# ATtiny4313_PN532_I2CMUX.net
KiCad netlist of a schematic drawn in EAGLE
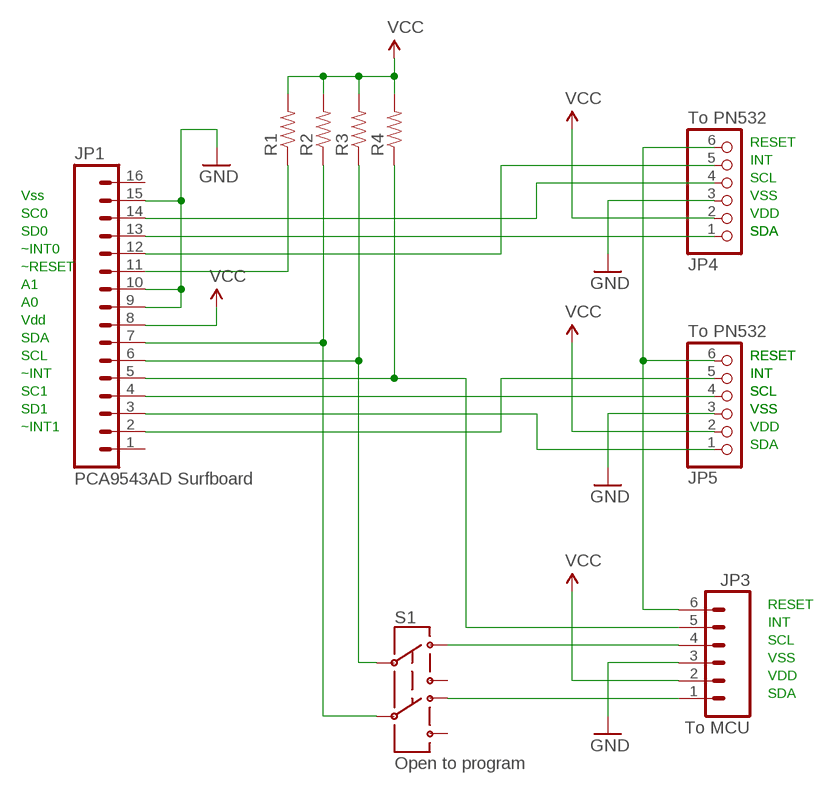
[diagram p0: schematic, sheet 1]

(export (version "E")
  (design (tool "Eeschema 10.0.6"))
  (components
    (comp (ref "JP1")
      (value "PCA9543AD Surfboard")
      (footprint "eagle-import:1X16_MACHINE-PIN-HEADER_LOCK.004")
      (libsource (lib "eagle-import") (part "M16MACHIINE-PIN_LOCK"))
    )
    (comp (ref "JP3")
      (value "To MCU")
      (footprint "eagle-import:1X06_LONGPADS")
      (libsource (lib "eagle-import") (part "M06LONGPADS"))
    )
    (comp (ref "JP4")
      (value "To PN532")
      (footprint "eagle-import:1X06_90")
      (libsource (lib "eagle-import") (part "PINHD-1X6/90"))
    )
    (comp (ref "JP5")
      (value "To PN532")
      (footprint "eagle-import:1X06_90")
      (libsource (lib "eagle-import") (part "PINHD-1X6/90"))
    )
    (comp (ref "R1")
      (value "RESISTORAXIAL-0.3")
      (footprint "eagle-import:AXIAL-0.3")
      (libsource (lib "eagle-import") (part "RESISTORAXIAL-0.3"))
    )
    (comp (ref "R2")
      (value "RESISTORAXIAL-0.3")
      (footprint "eagle-import:AXIAL-0.3")
      (libsource (lib "eagle-import") (part "RESISTORAXIAL-0.3"))
    )
    (comp (ref "R3")
      (value "RESISTORAXIAL-0.3")
      (footprint "eagle-import:AXIAL-0.3")
      (libsource (lib "eagle-import") (part "RESISTORAXIAL-0.3"))
    )
    (comp (ref "R4")
      (value "RESISTORAXIAL-0.3")
      (footprint "eagle-import:AXIAL-0.3")
      (libsource (lib "eagle-import") (part "RESISTORAXIAL-0.3"))
    )
    (comp (ref "S1")
      (value "Open to program")
      (footprint "eagle-import:OS")
      (libsource (lib "eagle-import") (part "SWITCH-DPDTOS"))
    )
  )
  (nets
    (net (code "1") (name "GND") (class "Default")
      (node (ref "JP1") (pin "10") (pinfunction "10_10") (pintype "passive"))
      (node (ref "JP1") (pin "15") (pinfunction "15_15") (pintype "passive"))
      (node (ref "JP1") (pin "9") (pinfunction "9_9") (pintype "passive"))
      (node (ref "JP3") (pin "3") (pinfunction "3_3") (pintype "passive"))
      (node (ref "JP4") (pin "3") (pinfunction "3_3") (pintype "passive"))
      (node (ref "JP5") (pin "3") (pinfunction "3_3") (pintype "passive"))
    )
    (net (code "2") (name "Net-(JP1-Pad2)") (class "Default")
      (node (ref "JP1") (pin "2") (pinfunction "2_2") (pintype "passive"))
      (node (ref "JP5") (pin "5") (pinfunction "5_5") (pintype "passive"))
    )
    (net (code "3") (name "Net-(JP1-Pad3)") (class "Default")
      (node (ref "JP1") (pin "3") (pinfunction "3_3") (pintype "passive"))
      (node (ref "JP5") (pin "1") (pinfunction "1_1") (pintype "passive"))
    )
    (net (code "4") (name "Net-(JP1-Pad4)") (class "Default")
      (node (ref "JP1") (pin "4") (pinfunction "4_4") (pintype "passive"))
      (node (ref "JP5") (pin "4") (pinfunction "4_4") (pintype "passive"))
    )
    (net (code "5") (name "Net-(JP1-Pad12)") (class "Default")
      (node (ref "JP1") (pin "12") (pinfunction "12_12") (pintype "passive"))
      (node (ref "JP4") (pin "5") (pinfunction "5_5") (pintype "passive"))
    )
    (net (code "6") (name "Net-(JP1-Pad13)") (class "Default")
      (node (ref "JP1") (pin "13") (pinfunction "13_13") (pintype "passive"))
      (node (ref "JP4") (pin "1") (pinfunction "1_1") (pintype "passive"))
    )
    (net (code "7") (name "Net-(JP1-Pad14)") (class "Default")
      (node (ref "JP1") (pin "14") (pinfunction "14_14") (pintype "passive"))
      (node (ref "JP4") (pin "4") (pinfunction "4_4") (pintype "passive"))
    )
    (net (code "8") (name "Net-(JP3-Pad1)") (class "Default")
      (node (ref "JP3") (pin "1") (pinfunction "1_1") (pintype "passive"))
      (node (ref "S1") (pin "4") (pinfunction "4_4") (pintype "bidirectional"))
    )
    (net (code "9") (name "Net-(JP3-Pad4)") (class "Default")
      (node (ref "JP3") (pin "4") (pinfunction "4_4") (pintype "passive"))
      (node (ref "S1") (pin "1") (pinfunction "1_1") (pintype "bidirectional"))
    )
    (net (code "10") (name "Net-(JP3-Pad6)") (class "Default")
      (node (ref "JP3") (pin "6") (pinfunction "6_6") (pintype "passive"))
      (node (ref "JP4") (pin "6") (pinfunction "6_6") (pintype "passive"))
      (node (ref "JP5") (pin "6") (pinfunction "6_6") (pintype "passive"))
    )
    (net (code "11") (name "Net-(R1-1)") (class "Default")
      (node (ref "JP1") (pin "11") (pinfunction "11_11") (pintype "passive"))
      (node (ref "R1") (pin "P$1") (pinfunction "1_P$1") (pintype "passive"))
    )
    (net (code "12") (name "Net-(R2-1)") (class "Default")
      (node (ref "JP1") (pin "7") (pinfunction "7_7") (pintype "passive"))
      (node (ref "R2") (pin "P$1") (pinfunction "1_P$1") (pintype "passive"))
      (node (ref "S1") (pin "5") (pinfunction "5_5") (pintype "bidirectional"))
    )
    (net (code "13") (name "Net-(R3-1)") (class "Default")
      (node (ref "JP1") (pin "6") (pinfunction "6_6") (pintype "passive"))
      (node (ref "R3") (pin "P$1") (pinfunction "1_P$1") (pintype "passive"))
      (node (ref "S1") (pin "2") (pinfunction "2_2") (pintype "bidirectional"))
    )
    (net (code "14") (name "Net-(R4-1)") (class "Default")
      (node (ref "JP1") (pin "5") (pinfunction "5_5") (pintype "passive"))
      (node (ref "JP3") (pin "5") (pinfunction "5_5") (pintype "passive"))
      (node (ref "R4") (pin "P$1") (pinfunction "1_P$1") (pintype "passive"))
    )
    (net (code "15") (name "VCC") (class "Default")
      (node (ref "JP1") (pin "8") (pinfunction "8_8") (pintype "passive"))
      (node (ref "JP3") (pin "2") (pinfunction "2_2") (pintype "passive"))
      (node (ref "JP4") (pin "2") (pinfunction "2_2") (pintype "passive"))
      (node (ref "JP5") (pin "2") (pinfunction "2_2") (pintype "passive"))
      (node (ref "R1") (pin "P$2") (pinfunction "2_P$2") (pintype "passive"))
      (node (ref "R2") (pin "P$2") (pinfunction "2_P$2") (pintype "passive"))
      (node (ref "R3") (pin "P$2") (pinfunction "2_P$2") (pintype "passive"))
      (node (ref "R4") (pin "P$2") (pinfunction "2_P$2") (pintype "passive"))
    )
    (net (code "16") (name "unconnected-(JP1-Pad1)") (class "Default")
      (node (ref "JP1") (pin "1") (pinfunction "1_1") (pintype "passive"))
    )
    (net (code "17") (name "unconnected-(JP1-Pad16)") (class "Default")
      (node (ref "JP1") (pin "16") (pinfunction "16_16") (pintype "passive"))
    )
    (net (code "18") (name "unconnected-(S1-Pad3)") (class "Default")
      (node (ref "S1") (pin "3") (pinfunction "3_3") (pintype "bidirectional"))
    )
    (net (code "19") (name "unconnected-(S1-Pad6)") (class "Default")
      (node (ref "S1") (pin "6") (pinfunction "6_6") (pintype "bidirectional"))
    )
  )
)
